# Wheatstone_bridge.net
KiCad netlist of a schematic drawn in Altium Designer
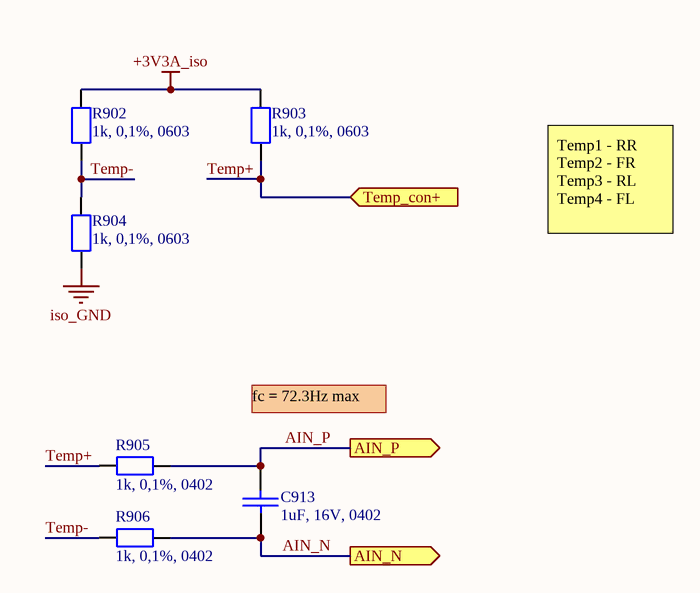
[diagram p0: Wheatstone_bridge.SchDoc]

(export (version "E")
  (design (tool "Eeschema 10.0.6"))
  (components
    (comp (ref "C913")
      (value "1uF, 16V, 0402")
      (footprint "CAP [0402] 1005")
      (description "Default capacitor part")
      (libsource (lib "Formula Student Team Tallinn (Estonia)") (part "Capacitor"))
    )
    (comp (ref "R902")
      (value "1k, 0,1%, 0603")
      (footprint "RES [0603] 1608")
      (description "Fixed Resistor, Thin Film, 0.1W, 1000ohm, 75V, 0.1% +/-Tol, 25ppm/Cel, Surface Mount, 0603")
      (fields
        (field (name "MANUFACTURER") "Panasonic")
        (field (name "MANUFACTURER PART NUMBER") "ERA-3AEB102V")
      )
      (libsource (lib "Formula Student Team Tallinn (Estonia)") (part "Resistor"))
    )
    (comp (ref "R903")
      (value "1k, 0,1%, 0603")
      (footprint "RES [0603] 1608")
      (description "Fixed Resistor, Thin Film, 0.1W, 1000ohm, 75V, 0.1% +/-Tol, 25ppm/Cel, Surface Mount, 0603")
      (fields
        (field (name "MANUFACTURER") "Panasonic")
        (field (name "MANUFACTURER PART NUMBER") "ERA-3AEB102V")
      )
      (libsource (lib "Formula Student Team Tallinn (Estonia)") (part "Resistor"))
    )
    (comp (ref "R904")
      (value "1k, 0,1%, 0603")
      (footprint "RES [0603] 1608")
      (description "Fixed Resistor, Thin Film, 0.1W, 1000ohm, 75V, 0.1% +/-Tol, 25ppm/Cel, Surface Mount, 0603")
      (fields
        (field (name "MANUFACTURER") "Panasonic")
        (field (name "MANUFACTURER PART NUMBER") "ERA-3AEB102V")
      )
      (libsource (lib "Formula Student Team Tallinn (Estonia)") (part "Resistor"))
    )
    (comp (ref "R905")
      (value "1k, 0,1%, 0402")
      (footprint "RES [0402] 1005")
      (description "Standard resistor part")
      (libsource (lib "Formula Student Team Tallinn (Estonia)") (part "Resistor"))
    )
    (comp (ref "R906")
      (value "1k, 0,1%, 0402")
      (footprint "RES [0402] 1005")
      (description "Standard resistor part")
      (libsource (lib "Formula Student Team Tallinn (Estonia)") (part "Resistor"))
    )
  )
  (nets
    (net (code "1") (name "+3V3A_iso") (class "Default")
      (node (ref "R902") (pin "1") (pinfunction "1_1") (pintype "passive"))
      (node (ref "R903") (pin "1") (pinfunction "1_1") (pintype "passive"))
    )
    (net (code "2") (name "/AIN_N") (class "Default")
      (node (ref "C913") (pin "2") (pinfunction "2_2") (pintype "passive"))
      (node (ref "R906") (pin "1") (pinfunction "1_1") (pintype "passive"))
    )
    (net (code "3") (name "/AIN_P") (class "Default")
      (node (ref "C913") (pin "1") (pinfunction "1_1") (pintype "passive"))
      (node (ref "R905") (pin "1") (pinfunction "1_1") (pintype "passive"))
    )
    (net (code "4") (name "/Temp+") (class "Default")
      (node (ref "R903") (pin "2") (pinfunction "2_2") (pintype "passive"))
      (node (ref "R905") (pin "2") (pinfunction "2_2") (pintype "passive"))
    )
    (net (code "5") (name "/Temp-") (class "Default")
      (node (ref "R902") (pin "2") (pinfunction "2_2") (pintype "passive"))
      (node (ref "R904") (pin "1") (pinfunction "1_1") (pintype "passive"))
      (node (ref "R906") (pin "2") (pinfunction "2_2") (pintype "passive"))
    )
    (net (code "6") (name "iso_GND") (class "Default")
      (node (ref "R904") (pin "2") (pinfunction "2_2") (pintype "passive"))
    )
  )
)
